# CH32V007E8R.net
KiCad netlist of a schematic drawn in Altium Designer
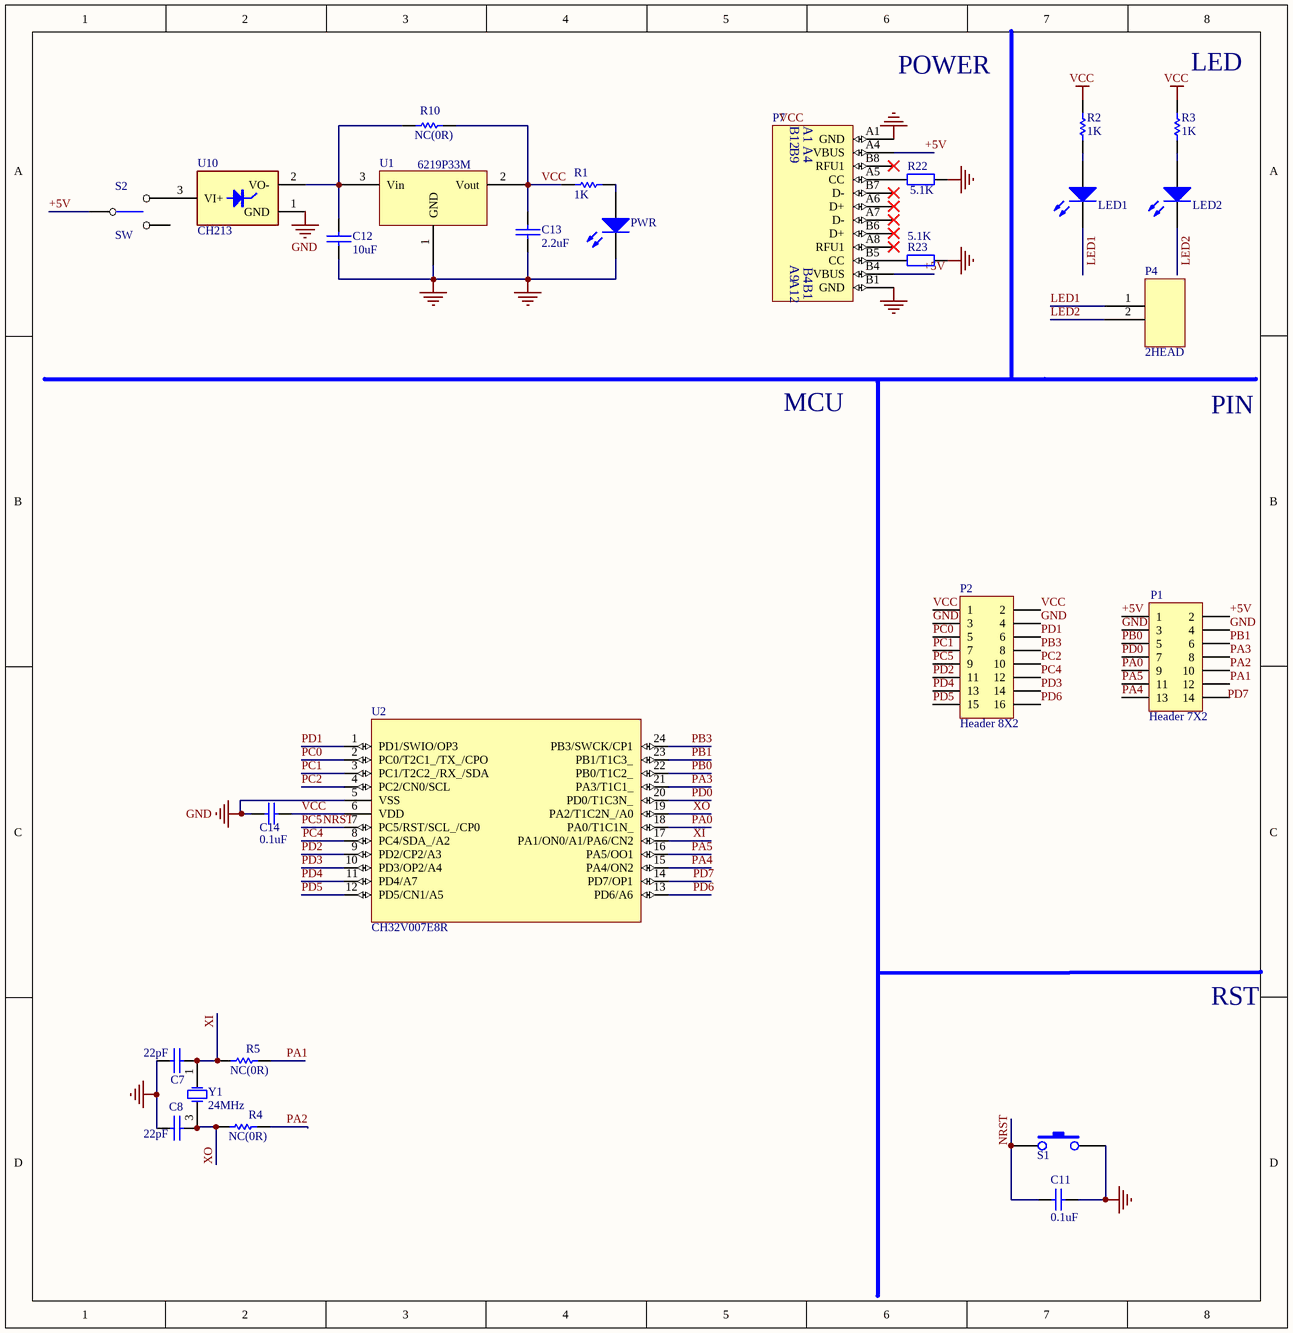
[diagram p0: CH32V007E8R.SchDoc]

(export (version "E")
  (design (tool "Eeschema 10.0.6"))
  (components
    (comp (ref "C7")
      (value "22pF")
      (footprint "0402_C")
      (description "Capacitor")
      (libsource (lib "*") (part "CAP"))
    )
    (comp (ref "C8")
      (value "22pF")
      (footprint "0402_C")
      (description "Capacitor")
      (libsource (lib "*") (part "CAP"))
    )
    (comp (ref "C11")
      (value "0.1uF")
      (footprint "0402_C")
      (description "Capacitor")
      (fields (field (name "PUBLISHER") "Altium Limited"))
      (libsource (lib "*") (part "Cap"))
    )
    (comp (ref "C12")
      (value "10uF")
      (footprint "0603_C")
      (description "Capacitor")
      (libsource (lib "wch_sch_others") (part "CAP"))
    )
    (comp (ref "C13")
      (value "2.2uF")
      (footprint "0402_C")
      (description "Capacitor")
      (libsource (lib "wch_sch_others") (part "CAP"))
    )
    (comp (ref "C14")
      (value "0.1uF")
      (footprint "0603_C")
      (description "Capacitor")
      (fields (field (name "PUBLISHER") "Altium Limited"))
      (libsource (lib "*") (part "Cap"))
    )
    (comp (ref "LED1")
      (value "LED1   blue")
      (footprint "0603+")
      (description "Typical INFRARED GaAs LED")
      (fields (field (name "PUBLISHER") "Altium Limited"))
      (libsource (lib "*") (part "LED0"))
    )
    (comp (ref "LED2")
      (value "LED2  blue")
      (footprint "0603+")
      (description "Typical INFRARED GaAs LED")
      (fields (field (name "PUBLISHER") "Altium Limited"))
      (libsource (lib "*") (part "LED0"))
    )
    (comp (ref "P1")
      (value "Header 7X2")
      (footprint "HDR2X7")
      (description "Header, 7-Pin, Dual row")
      (fields (field (name "PUBLISHER") "Altium Limited"))
      (libsource (lib "Miscellaneous Connectors") (part "Header 7X2"))
    )
    (comp (ref "P2")
      (value "Header 8X2")
      (footprint "HDR2X8")
      (description "Header, 8-Pin, Dual row")
      (fields (field (name "PUBLISHER") "Altium Limited"))
      (libsource (lib "Miscellaneous Connectors") (part "Header 8X2"))
    )
    (comp (ref "P4") (value "2HEAD") (footprint "SIP2-2.54mm") (libsource (lib "*") (part "2HEAD")))
    (comp (ref "P7")
      (value "TYPE-C")
      (footprint "TYPE-C-Receptacle-2.0")
      (libsource (lib "*") (part "TYPE-C1"))
    )
    (comp (ref "PWR")
      (value "POWER  red")
      (footprint "0603+")
      (description "Typical INFRARED GaAs LED")
      (fields (field (name "PUBLISHER") "Altium Limited"))
      (libsource (lib "") (part "LED0_1"))
    )
    (comp (ref "R1")
      (value "1K")
      (footprint "0402")
      (description "Semiconductor Resistor")
      (fields (field (name "PUBLISHER") "Altium Limited"))
      (libsource (lib "*") (part "Res Semi"))
    )
    (comp (ref "R2")
      (value "1K")
      (footprint "0402")
      (description "Semiconductor Resistor")
      (fields (field (name "PUBLISHER") "Altium Limited"))
      (libsource (lib "*") (part "Res Semi"))
    )
    (comp (ref "R3")
      (value "1K")
      (footprint "0402")
      (description "Semiconductor Resistor")
      (fields (field (name "PUBLISHER") "Altium Limited"))
      (libsource (lib "*") (part "Res Semi"))
    )
    (comp (ref "R4")
      (value "NC(0R)")
      (footprint "0402")
      (description "Semiconductor Resistor")
      (fields (field (name "Comment") "0R") (field (name "PUBLISHER") "Altium Limited"))
      (libsource (lib "*") (part "Res Semi"))
    )
    (comp (ref "R5")
      (value "NC(0R)")
      (footprint "0402")
      (description "Semiconductor Resistor")
      (fields (field (name "Comment") "0R") (field (name "PUBLISHER") "Altium Limited"))
      (libsource (lib "*") (part "Res Semi"))
    )
    (comp (ref "R10")
      (value "NC(0R)")
      (footprint "0402")
      (description "Semiconductor Resistor")
      (fields (field (name "Comment") "0R") (field (name "PUBLISHER") "Altium Limited"))
      (libsource (lib "*") (part "Res Semi"))
    )
    (comp (ref "R22")
      (value "5.1K")
      (footprint "0402")
      (description "Resistor")
      (libsource (lib "Miscellaneous Devices") (part "Res2"))
    )
    (comp (ref "R23")
      (value "5.1K")
      (footprint "0402")
      (description "Resistor")
      (libsource (lib "Miscellaneous Devices") (part "Res2"))
    )
    (comp (ref "S1") (value "NRST") (footprint "SMD_6.1x3.65x2.5mm-KEY") (libsource (lib "*") (part "KEY")))
    (comp (ref "S2") (value "SW") (footprint "SW1") (libsource (lib "*") (part "SW")))
    (comp (ref "U1")
      (value "6219P33M")
      (footprint "SOT-23")
      (libsource (lib "wch_sch_others") (part "6219P33M"))
    )
    (comp (ref "U2")
      (value "CH32V007E8R")
      (footprint "QSOP24")
      (description "RISC-V MCU, ADC/OPA/CMP/2*UART/I2C/SPI")
      (libsource (lib "DHXXXSCH") (part "CH32V007E8R6"))
    )
    (comp (ref "U10")
      (value "CH213")
      (footprint "SOT-23-3")
      (description "Ideal Diode 5V*1A")
      (libsource (lib "CHXXX") (part "CH213E"))
    )
    (comp (ref "Y1")
      (value "24MHz")
      (footprint "XT3225")
      (description "Crystal Oscillator")
      (fields (field (name "PUBLISHER") "Altium Limited"))
      (libsource (lib "*") (part "XTAL"))
    )
  )
  (nets
    (net (code "1") (name "/+5V") (class "Default")
      (node (ref "P1") (pin "1") (pinfunction "1_1") (pintype "passive"))
      (node (ref "P1") (pin "2") (pinfunction "2_2") (pintype "passive"))
      (node (ref "P7") (pin "A4") (pinfunction "VBUS_A4") (pintype "bidirectional"))
      (node (ref "P7") (pin "B4") (pinfunction "VBUS_B4") (pintype "bidirectional"))
      (node (ref "S2") (pin "1") (pinfunction "1_1") (pintype "passive"))
    )
    (net (code "2") (name "/LED1") (class "Default")
      (node (ref "LED1") (pin "2") (pinfunction "K_2") (pintype "passive"))
      (node (ref "P4") (pin "1") (pintype "passive"))
    )
    (net (code "3") (name "/LED2") (class "Default")
      (node (ref "LED2") (pin "2") (pinfunction "K_2") (pintype "passive"))
      (node (ref "P4") (pin "2") (pintype "passive"))
    )
    (net (code "4") (name "/NRST") (class "Default")
      (node (ref "C11") (pin "2") (pinfunction "2_2") (pintype "passive"))
      (node (ref "P2") (pin "9") (pinfunction "9_9") (pintype "passive"))
      (node (ref "S1") (pin "1") (pinfunction "1_1") (pintype "passive"))
      (node (ref "U2") (pin "7") (pinfunction "PC5/RST/SCL_/CP0_7") (pintype "bidirectional"))
    )
    (net (code "5") (name "/PA0") (class "Default")
      (node (ref "P1") (pin "9") (pinfunction "9_9") (pintype "passive"))
      (node (ref "U2") (pin "18") (pinfunction "PA0/T1C1N__18") (pintype "bidirectional"))
    )
    (net (code "6") (name "/PA1") (class "Default")
      (node (ref "P1") (pin "12") (pinfunction "12_12") (pintype "passive"))
      (node (ref "R5") (pin "2") (pinfunction "2_2") (pintype "passive"))
    )
    (net (code "7") (name "/PA2") (class "Default")
      (node (ref "P1") (pin "10") (pinfunction "10_10") (pintype "passive"))
      (node (ref "R4") (pin "2") (pinfunction "2_2") (pintype "passive"))
    )
    (net (code "8") (name "/PA3") (class "Default")
      (node (ref "P1") (pin "8") (pinfunction "8_8") (pintype "passive"))
      (node (ref "U2") (pin "21") (pinfunction "PA3/T1C1__21") (pintype "bidirectional"))
    )
    (net (code "9") (name "/PA4") (class "Default")
      (node (ref "P1") (pin "13") (pinfunction "13_13") (pintype "passive"))
      (node (ref "U2") (pin "15") (pinfunction "PA4/ON2_15") (pintype "bidirectional"))
    )
    (net (code "10") (name "/PA5") (class "Default")
      (node (ref "P1") (pin "11") (pinfunction "11_11") (pintype "passive"))
      (node (ref "U2") (pin "16") (pinfunction "PA5/OO1_16") (pintype "bidirectional"))
    )
    (net (code "11") (name "/PB0") (class "Default")
      (node (ref "P1") (pin "5") (pinfunction "5_5") (pintype "passive"))
      (node (ref "U2") (pin "22") (pinfunction "PB0/T1C2__22") (pintype "bidirectional"))
    )
    (net (code "12") (name "/PB1") (class "Default")
      (node (ref "P1") (pin "6") (pinfunction "6_6") (pintype "passive"))
      (node (ref "U2") (pin "23") (pinfunction "PB1/T1C3__23") (pintype "bidirectional"))
    )
    (net (code "13") (name "/PB3") (class "Default")
      (node (ref "P2") (pin "8") (pinfunction "8_8") (pintype "passive"))
      (node (ref "U2") (pin "24") (pinfunction "PB3/SWCK/CP1_24") (pintype "bidirectional"))
    )
    (net (code "14") (name "/PC0") (class "Default")
      (node (ref "P2") (pin "5") (pinfunction "5_5") (pintype "passive"))
      (node (ref "U2") (pin "2") (pinfunction "PC0/T2C1_/TX_/CPO_2") (pintype "bidirectional"))
    )
    (net (code "15") (name "/PC1") (class "Default")
      (node (ref "P2") (pin "7") (pinfunction "7_7") (pintype "passive"))
      (node (ref "U2") (pin "3") (pinfunction "PC1/T2C2_/RX_/SDA_3") (pintype "bidirectional"))
    )
    (net (code "16") (name "/PC2") (class "Default")
      (node (ref "P2") (pin "10") (pinfunction "10_10") (pintype "passive"))
      (node (ref "U2") (pin "4") (pinfunction "PC2/CN0/SCL_4") (pintype "bidirectional"))
    )
    (net (code "17") (name "/PC4") (class "Default")
      (node (ref "P2") (pin "12") (pinfunction "12_12") (pintype "passive"))
      (node (ref "U2") (pin "8") (pinfunction "PC4/SDA_/A2_8") (pintype "bidirectional"))
    )
    (net (code "18") (name "/PD0") (class "Default")
      (node (ref "P1") (pin "7") (pinfunction "7_7") (pintype "passive"))
      (node (ref "U2") (pin "20") (pinfunction "PD0/T1C3N__20") (pintype "bidirectional"))
    )
    (net (code "19") (name "/PD1") (class "Default")
      (node (ref "P2") (pin "6") (pinfunction "6_6") (pintype "passive"))
      (node (ref "U2") (pin "1") (pinfunction "PD1/SWIO/OP3_1") (pintype "bidirectional"))
    )
    (net (code "20") (name "/PD2") (class "Default")
      (node (ref "P2") (pin "11") (pinfunction "11_11") (pintype "passive"))
      (node (ref "U2") (pin "9") (pinfunction "PD2/CP2/A3_9") (pintype "bidirectional"))
    )
    (net (code "21") (name "/PD3") (class "Default")
      (node (ref "P2") (pin "14") (pinfunction "14_14") (pintype "passive"))
      (node (ref "U2") (pin "10") (pinfunction "PD3/OP2/A4_10") (pintype "bidirectional"))
    )
    (net (code "22") (name "/PD4") (class "Default")
      (node (ref "P2") (pin "13") (pinfunction "13_13") (pintype "passive"))
      (node (ref "U2") (pin "11") (pinfunction "PD4/A7_11") (pintype "bidirectional"))
    )
    (net (code "23") (name "/PD5") (class "Default")
      (node (ref "P2") (pin "15") (pinfunction "15_15") (pintype "passive"))
      (node (ref "U2") (pin "12") (pinfunction "PD5/CN1/A5_12") (pintype "bidirectional"))
    )
    (net (code "24") (name "/PD6") (class "Default")
      (node (ref "P2") (pin "16") (pinfunction "16_16") (pintype "passive"))
      (node (ref "U2") (pin "13") (pinfunction "PD6/A6_13") (pintype "bidirectional"))
    )
    (net (code "25") (name "/PD7") (class "Default")
      (node (ref "U2") (pin "14") (pinfunction "PD7/OP1_14") (pintype "bidirectional"))
    )
    (net (code "26") (name "/XI") (class "Default")
      (node (ref "C7") (pin "2") (pinfunction "2_2") (pintype "passive"))
      (node (ref "R5") (pin "1") (pinfunction "1_1") (pintype "passive"))
      (node (ref "U2") (pin "17") (pinfunction "PA1/ON0/A1/PA6/CN2_17") (pintype "bidirectional"))
      (node (ref "Y1") (pin "1") (pinfunction "OSC1_1") (pintype "passive"))
    )
    (net (code "27") (name "/XO") (class "Default")
      (node (ref "C8") (pin "2") (pinfunction "2_2") (pintype "passive"))
      (node (ref "R4") (pin "1") (pinfunction "1_1") (pintype "passive"))
      (node (ref "U2") (pin "19") (pinfunction "PA2/T1C2N_/A0_19") (pintype "bidirectional"))
      (node (ref "Y1") (pin "3") (pinfunction "OSC2_3") (pintype "passive"))
    )
    (net (code "28") (name "GND") (class "Default")
      (node (ref "C11") (pin "1") (pinfunction "1_1") (pintype "passive"))
      (node (ref "C12") (pin "2") (pinfunction "2_2") (pintype "passive"))
      (node (ref "C13") (pin "1") (pinfunction "1_1") (pintype "passive"))
      (node (ref "C14") (pin "1") (pinfunction "1_1") (pintype "passive"))
      (node (ref "C7") (pin "1") (pinfunction "1_1") (pintype "passive"))
      (node (ref "C8") (pin "1") (pinfunction "1_1") (pintype "passive"))
      (node (ref "P1") (pin "3") (pinfunction "3_3") (pintype "passive"))
      (node (ref "P1") (pin "4") (pinfunction "4_4") (pintype "passive"))
      (node (ref "P2") (pin "3") (pinfunction "3_3") (pintype "passive"))
      (node (ref "P2") (pin "4") (pinfunction "4_4") (pintype "passive"))
      (node (ref "P7") (pin "A1") (pinfunction "GND_A1") (pintype "bidirectional"))
      (node (ref "P7") (pin "B1") (pinfunction "GND_B1") (pintype "bidirectional"))
      (node (ref "PWR") (pin "2") (pinfunction "K_2") (pintype "passive"))
      (node (ref "R22") (pin "2") (pinfunction "2_2") (pintype "passive"))
      (node (ref "R23") (pin "2") (pinfunction "2_2") (pintype "passive"))
      (node (ref "S1") (pin "2") (pinfunction "2_2") (pintype "passive"))
      (node (ref "U1") (pin "1") (pinfunction "GND_1") (pintype "passive"))
      (node (ref "U10") (pin "1") (pinfunction "GND_1") (pintype "power_in"))
      (node (ref "U2") (pin "5") (pinfunction "VSS_5") (pintype "power_in"))
    )
    (net (code "29") (name "Net-(LED1-A)") (class "Default")
      (node (ref "LED1") (pin "1") (pinfunction "A_1") (pintype "passive"))
      (node (ref "R2") (pin "2") (pinfunction "2_2") (pintype "passive"))
    )
    (net (code "30") (name "Net-(LED2-A)") (class "Default")
      (node (ref "LED2") (pin "1") (pinfunction "A_1") (pintype "passive"))
      (node (ref "R3") (pin "2") (pinfunction "2_2") (pintype "passive"))
    )
    (net (code "31") (name "Net-(P7-CC-PadA5)") (class "Default")
      (node (ref "P7") (pin "A5") (pinfunction "CC_A5") (pintype "bidirectional"))
      (node (ref "R22") (pin "1") (pinfunction "1_1") (pintype "passive"))
    )
    (net (code "32") (name "Net-(P7-CC-PadB5)") (class "Default")
      (node (ref "P7") (pin "B5") (pinfunction "CC_B5") (pintype "bidirectional"))
      (node (ref "R23") (pin "1") (pinfunction "1_1") (pintype "passive"))
    )
    (net (code "33") (name "Net-(PWR-A)") (class "Default")
      (node (ref "PWR") (pin "1") (pinfunction "A_1") (pintype "passive"))
      (node (ref "R1") (pin "1") (pinfunction "1_1") (pintype "passive"))
    )
    (net (code "34") (name "Net-(U1-Vin)") (class "Default")
      (node (ref "C12") (pin "1") (pinfunction "1_1") (pintype "passive"))
      (node (ref "R10") (pin "1") (pinfunction "1_1") (pintype "passive"))
      (node (ref "U1") (pin "3") (pinfunction "Vin_3") (pintype "passive"))
      (node (ref "U10") (pin "2") (pinfunction "VO-_2") (pintype "power_in"))
    )
    (net (code "35") (name "Net-(U10-VI+)") (class "Default")
      (node (ref "S2") (pin "3") (pinfunction "3_3") (pintype "passive"))
      (node (ref "U10") (pin "3") (pinfunction "VI+_3") (pintype "power_in"))
    )
    (net (code "36") (name "VCC") (class "Default")
      (node (ref "C13") (pin "2") (pinfunction "2_2") (pintype "passive"))
      (node (ref "C14") (pin "2") (pinfunction "2_2") (pintype "passive"))
      (node (ref "P2") (pin "1") (pinfunction "1_1") (pintype "passive"))
      (node (ref "P2") (pin "2") (pinfunction "2_2") (pintype "passive"))
      (node (ref "R1") (pin "2") (pinfunction "2_2") (pintype "passive"))
      (node (ref "R10") (pin "2") (pinfunction "2_2") (pintype "passive"))
      (node (ref "R2") (pin "1") (pinfunction "1_1") (pintype "passive"))
      (node (ref "R3") (pin "1") (pinfunction "1_1") (pintype "passive"))
      (node (ref "U1") (pin "2") (pinfunction "Vout_2") (pintype "passive"))
      (node (ref "U2") (pin "6") (pinfunction "VDD_6") (pintype "power_in"))
    )
    (net (code "37") (name "unconnected-(P1-Pad14)") (class "Default")
      (node (ref "P1") (pin "14") (pinfunction "14_14") (pintype "passive"))
    )
    (net (code "38") (name "unconnected-(P7-D+-PadA6)") (class "Default")
      (node (ref "P7") (pin "A6") (pinfunction "D+_A6") (pintype "bidirectional+no_connect"))
    )
    (net (code "39") (name "unconnected-(P7-D+-PadB6)") (class "Default")
      (node (ref "P7") (pin "B6") (pinfunction "D+_B6") (pintype "bidirectional+no_connect"))
    )
    (net (code "40") (name "unconnected-(P7-D--PadA7)") (class "Default")
      (node (ref "P7") (pin "A7") (pinfunction "D-_A7") (pintype "bidirectional+no_connect"))
    )
    (net (code "41") (name "unconnected-(P7-D--PadB7)") (class "Default")
      (node (ref "P7") (pin "B7") (pinfunction "D-_B7") (pintype "bidirectional+no_connect"))
    )
    (net (code "42") (name "unconnected-(P7-RFU1-PadA8)") (class "Default")
      (node (ref "P7") (pin "A8") (pinfunction "RFU1_A8") (pintype "bidirectional+no_connect"))
    )
    (net (code "43") (name "unconnected-(P7-RFU1-PadB8)") (class "Default")
      (node (ref "P7") (pin "B8") (pinfunction "RFU1_B8") (pintype "bidirectional+no_connect"))
    )
    (net (code "44") (name "unconnected-(S2-Pad2)") (class "Default")
      (node (ref "S2") (pin "2") (pinfunction "2_2") (pintype "passive"))
    )
  )
)
